# Power_Supply.net
KiCad netlist of a schematic drawn in Altium Designer
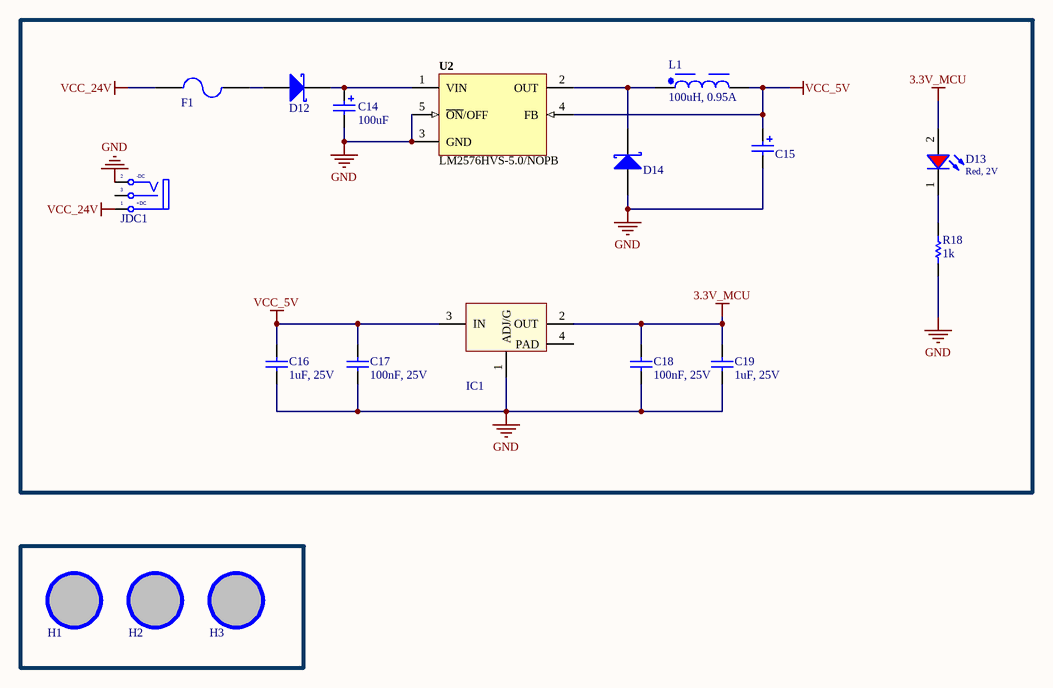
[diagram p0: Power_Supply.SchDoc]

(export (version "E")
  (design (tool "Eeschema 10.0.6"))
  (components
    (comp (ref "C14")
      (value "100uF")
      (footprint "WCAP-ATG8_D8H11.5")
      (description "WCAP-ATG8 Aluminum Electrolytic Capacitor, Radial THT, D8xH11.5mm, 100uF, 50V")
      (fields
        (field (name "MANUFACTURER") "Wurth Elektronik")
        (field (name "MANUFACTURER PART NUMBER") "860010674014")
      )
      (libsource (lib "Altium_WCAP-ATG8 (rev22a)") (part "860010674014"))
    )
    (comp (ref "C15")
      (value "1000uF")
      (footprint "WCAP-ATG8_D13H25")
      (description "WCAP-ATG8 Aluminum Electrolytic Capacitor, Radial THT, D13xH25mm, 1000uF, 50V")
      (fields
        (field (name "MANUFACTURER") "Wurth Elektronik")
        (field (name "MANUFACTURER PART NUMBER") "860010678024")
      )
      (libsource (lib "Altium_WCAP-ATG8 (rev22a)") (part "860010678024"))
    )
    (comp (ref "C16")
      (value "1uF, 25V")
      (footprint "WCAP-CSGP_0603_H=0.8mm_Reflow")
      (description "WCAP-CSGP Multilayer Ceramic Chip Capacitor, General Purpose, size 0603, X5R, 1uF, 25V")
      (fields
        (field (name "MANUFACTURER PART NUMBER") "885012106022")
        (field (name "MANUFACTURER") "Wurth Elektronik")
      )
      (libsource (lib "Altium_WCAP-CSGP (rev20a)") (part "885012106022"))
    )
    (comp (ref "C17")
      (value "100nF, 25V")
      (footprint "WCAP-CSGP_0603_H=0.8mm_Reflow")
      (description "WCAP-CSGP Multilayer Ceramic Chip Capacitor, General Purpose, size 0603, X7R, 100nF, 25V")
      (fields
        (field (name "MANUFACTURER PART NUMBER") "885012206071")
        (field (name "MANUFACTURER") "Wurth Elektronik")
      )
      (libsource (lib "Altium_WCAP-CSGP (rev20a)") (part "885012206071"))
    )
    (comp (ref "C18")
      (value "100nF, 25V")
      (footprint "WCAP-CSGP_0603_H=0.8mm_Reflow")
      (description "WCAP-CSGP Multilayer Ceramic Chip Capacitor, General Purpose, size 0603, X7R, 100nF, 25V")
      (fields
        (field (name "MANUFACTURER PART NUMBER") "885012206071")
        (field (name "MANUFACTURER") "Wurth Elektronik")
      )
      (libsource (lib "Altium_WCAP-CSGP (rev20a)") (part "885012206071"))
    )
    (comp (ref "C19")
      (value "1uF, 25V")
      (footprint "WCAP-CSGP_0603_H=0.8mm_Reflow")
      (description "WCAP-CSGP Multilayer Ceramic Chip Capacitor, General Purpose, size 0603, X5R, 1uF, 25V")
      (fields
        (field (name "MANUFACTURER PART NUMBER") "885012106022")
        (field (name "MANUFACTURER") "Wurth Elektronik")
      )
      (libsource (lib "Altium_WCAP-CSGP (rev20a)") (part "885012106022"))
    )
    (comp (ref "D12")
      (value "SS34")
      (footprint "SS34")
      (description "DIODE SCHOTTKY 40V 3A SMC")
      (fields (field (name "MFR") "onsemi") (field (name "PUBLISHER") "Altium Limited"))
      (libsource (lib "PIF_Library") (part "D Schottky"))
    )
    (comp (ref "D13")
      (value "Red, 2V")
      (footprint "WL-SMCW_0603_H=0.7mm")
      (description "WL-SMCW SMT Mono-color Chip LED Waterclear, size 0603, Red, 2V, 140deg")
      (fields (field (name "PART NUMBER") "150060RS75000") (field (name "PUBLISHER") "Wurth Elektronik"))
      (libsource (lib "Altium_WL-SMCW (rev20a)") (part "150060RS75000"))
    )
    (comp (ref "D14")
      (value "SS34")
      (footprint "SS34")
      (description "DIODE SCHOTTKY 40V 3A SMC")
      (fields (field (name "MFR") "onsemi") (field (name "PUBLISHER") "Altium Limited"))
      (libsource (lib "PIF_Library") (part "D Schottky"))
    )
    (comp (ref "F1")
      (value "0ZCG0150BF2C")
      (footprint "FUSE SMD")
      (description "PTC RESET FUSE 24V 1.5A 1812")
      (fields (field (name "MFR") "Bel Fuse Inc."))
      (libsource (lib "PIF_Library") (part "Fuse"))
    )
    (comp (ref "H1")
      (value "Hole")
      (footprint "LO KHOAN 3MM")
      (description "Hole 3mm")
      (libsource (lib "PIF_Library") (part "Hole"))
    )
    (comp (ref "H2")
      (value "Hole")
      (footprint "LO KHOAN 3MM")
      (description "Hole 3mm")
      (libsource (lib "PIF_Library") (part "Hole"))
    )
    (comp (ref "H3")
      (value "Hole")
      (footprint "LO KHOAN 3MM")
      (description "Hole 3mm")
      (libsource (lib "PIF_Library") (part "Hole"))
    )
    (comp (ref "IC1")
      (value "LM1117IMP-3.3/NOPB")
      (footprint "SOT223-4N")
      (description "IC REG LINEAR 3.3V 800MA SOT223")
      (fields (field (name "MFR") "Texas Instruments"))
      (libsource (lib "PIF_Library") (part "LM1117"))
    )
    (comp (ref "JDC1")
      (value "G-014-4")
      (footprint "DC-IN")
      (description "DC POWER JACK, MATES TO 5.5 X 2.")
      (fields (field (name "MFR") "GlobTek, Inc."))
      (libsource (lib "PIF_Library") (part "Jack DC"))
    )
    (comp (ref "L1")
      (value "100uH, 0.95A")
      (footprint "WE-PD2SR_7850")
      (description "WE-PD2SR SMT Power Inductor, size 7850, 100uH, 0.95A, 467mOhm")
      (fields
        (field (name "MANUFACTURER") "Wurth Elektronik")
        (field (name "MANUFACTURER PART NUMBER") "744787101")
      )
      (libsource (lib "WE-PD2SR (rev22a)") (part "744787101"))
    )
    (comp (ref "R18")
      (value "1k")
      (footprint "RES-SM-0603")
      (description "RES SMD 1K OHM 5% 1/4W 0603")
      (fields (field (name "MFR") "Rohm Semiconductor") (field (name "TOLERANCE") "±5%"))
      (libsource (lib "PIF_Library") (part "RESISTOR SMD"))
    )
    (comp (ref "U2")
      (value "LM2576HVS-5.0/NOPB")
      (footprint "TO263")
      (description "IC REG BUCK 5V 3A TO263-5")
      (libsource (lib "TechMT.VN_Lib_Project v2") (part "LM2576"))
    )
  )
  (nets
    (net (code "1") (name "3.3V_MCU") (class "Default")
      (node (ref "C18") (pin "2") (pinfunction "2_2") (pintype "passive"))
      (node (ref "C19") (pin "2") (pinfunction "2_2") (pintype "passive"))
      (node (ref "D13") (pin "2") (pinfunction "A_2") (pintype "passive"))
      (node (ref "IC1") (pin "2") (pinfunction "OUT_2") (pintype "passive"))
    )
    (net (code "2") (name "GND") (class "Default")
      (node (ref "C14") (pin "2") (pinfunction "N_2") (pintype "passive"))
      (node (ref "C15") (pin "2") (pinfunction "N_2") (pintype "passive"))
      (node (ref "C16") (pin "1") (pinfunction "1_1") (pintype "passive"))
      (node (ref "C17") (pin "1") (pinfunction "1_1") (pintype "passive"))
      (node (ref "C18") (pin "1") (pinfunction "1_1") (pintype "passive"))
      (node (ref "C19") (pin "1") (pinfunction "1_1") (pintype "passive"))
      (node (ref "D14") (pin "1") (pinfunction "A_1") (pintype "passive"))
      (node (ref "IC1") (pin "1") (pinfunction "ADJ/G_1") (pintype "passive"))
      (node (ref "JDC1") (pin "2") (pinfunction "TN_2") (pintype "passive"))
      (node (ref "R18") (pin "1") (pinfunction "1_1") (pintype "passive"))
      (node (ref "U2") (pin "3") (pinfunction "GND_3") (pintype "power_in"))
      (node (ref "U2") (pin "5") (pinfunction "~{ON}/OFF_5") (pintype "input"))
    )
    (net (code "3") (name "Net-(C14-P)") (class "Default")
      (node (ref "C14") (pin "1") (pinfunction "P_1") (pintype "passive"))
      (node (ref "D12") (pin "2") (pinfunction "K_2") (pintype "passive"))
      (node (ref "U2") (pin "1") (pinfunction "VIN_1") (pintype "power_in"))
    )
    (net (code "4") (name "Net-(D12-A)") (class "Default")
      (node (ref "D12") (pin "1") (pinfunction "A_1") (pintype "passive"))
      (node (ref "F1") (pin "2") (pinfunction "2_2") (pintype "passive"))
    )
    (net (code "5") (name "Net-(D13-K)") (class "Default")
      (node (ref "D13") (pin "1") (pinfunction "K_1") (pintype "passive"))
      (node (ref "R18") (pin "2") (pinfunction "2_2") (pintype "passive"))
    )
    (net (code "6") (name "Net-(D14-K)") (class "Default")
      (node (ref "D14") (pin "2") (pinfunction "K_2") (pintype "passive"))
      (node (ref "L1") (pin "1") (pinfunction "1_1") (pintype "passive"))
      (node (ref "U2") (pin "2") (pinfunction "OUT_2") (pintype "power_in"))
    )
    (net (code "7") (name "VCC_5V") (class "Default")
      (node (ref "C15") (pin "1") (pinfunction "P_1") (pintype "passive"))
      (node (ref "C16") (pin "2") (pinfunction "2_2") (pintype "passive"))
      (node (ref "C17") (pin "2") (pinfunction "2_2") (pintype "passive"))
      (node (ref "IC1") (pin "3") (pinfunction "IN_3") (pintype "passive"))
      (node (ref "L1") (pin "2") (pinfunction "2_2") (pintype "passive"))
      (node (ref "U2") (pin "4") (pinfunction "FB_4") (pintype "input"))
    )
    (net (code "8") (name "VCC_24V") (class "Default")
      (node (ref "F1") (pin "1") (pinfunction "1_1") (pintype "passive"))
      (node (ref "JDC1") (pin "1") (pinfunction "T_1") (pintype "passive"))
    )
    (net (code "9") (name "unconnected-(H1-Pad1)") (class "Default")
      (node (ref "H1") (pin "1") (pinfunction "1_1") (pintype "passive"))
    )
    (net (code "10") (name "unconnected-(H2-Pad1)") (class "Default")
      (node (ref "H2") (pin "1") (pinfunction "1_1") (pintype "passive"))
    )
    (net (code "11") (name "unconnected-(H3-Pad1)") (class "Default")
      (node (ref "H3") (pin "1") (pinfunction "1_1") (pintype "passive"))
    )
    (net (code "12") (name "unconnected-(IC1-PAD-Pad4)") (class "Default")
      (node (ref "IC1") (pin "4") (pinfunction "PAD_4") (pintype "passive"))
    )
    (net (code "13") (name "unconnected-(JDC1-S-Pad3)") (class "Default")
      (node (ref "JDC1") (pin "3") (pinfunction "S_3") (pintype "power_in"))
    )
  )
)
